# Lamp_Daughter_Board_V0_1.net
KiCad netlist of a schematic drawn in EasyEDA Pro
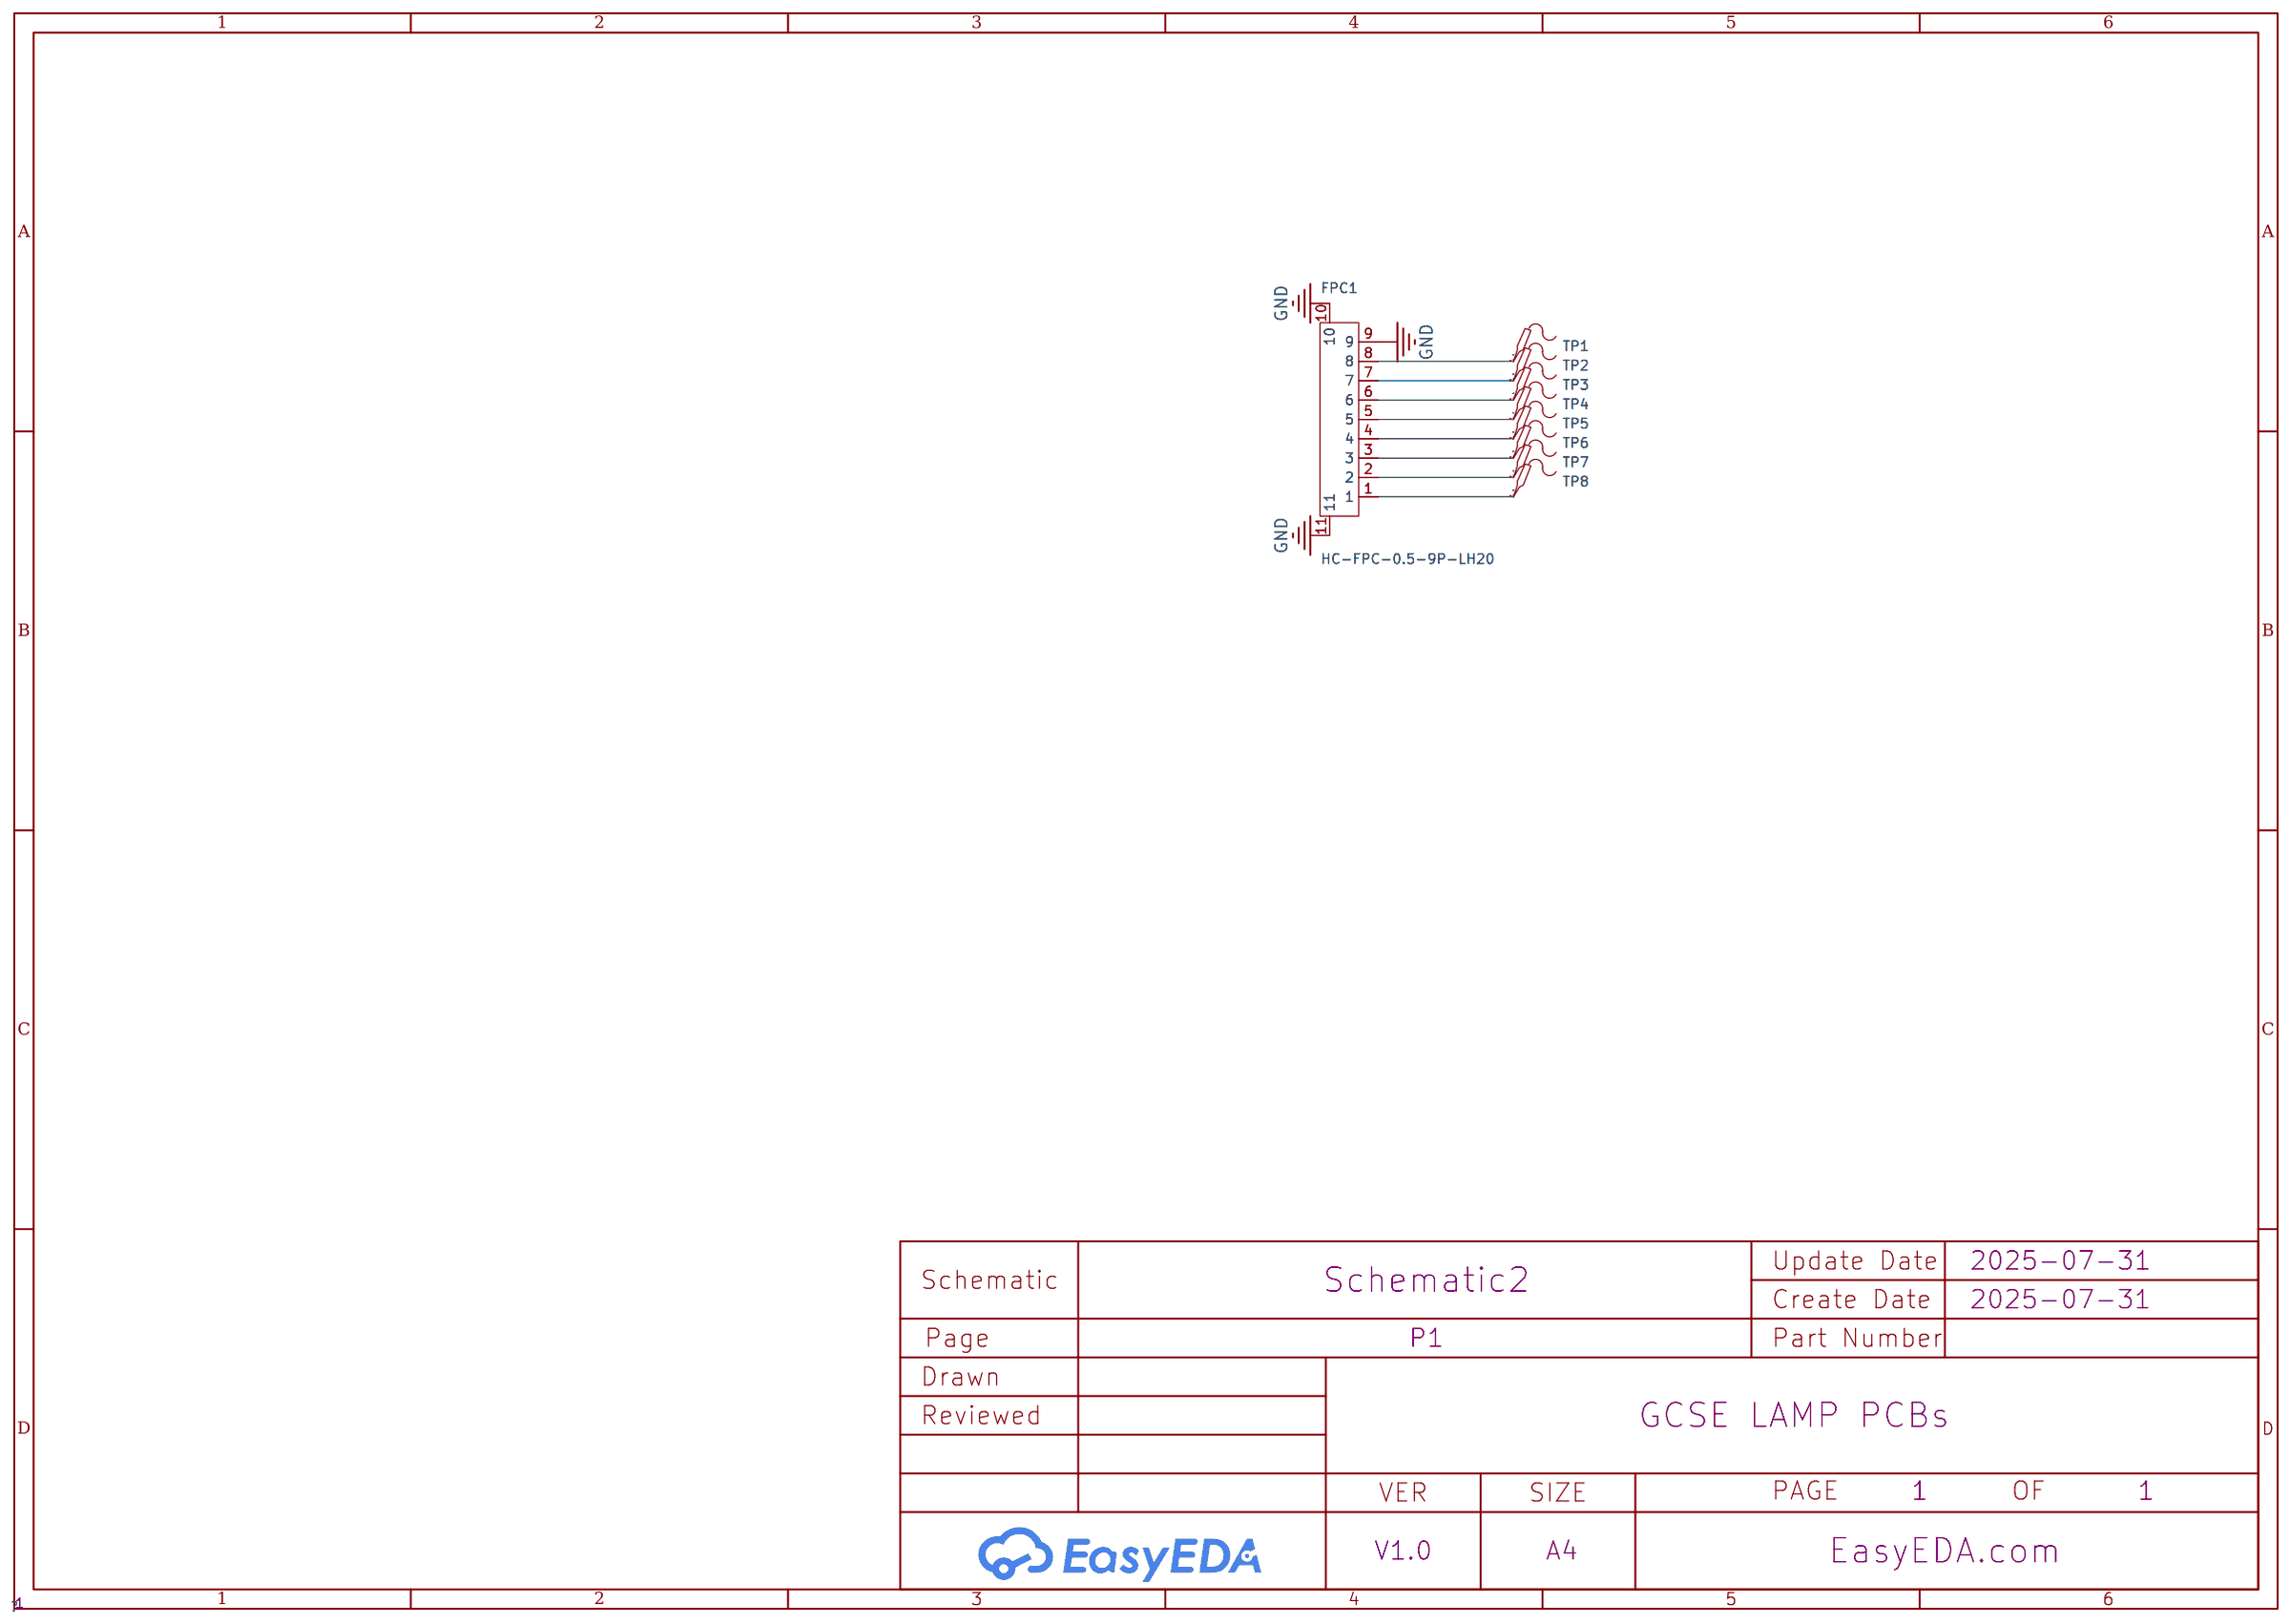
[diagram p0: schematic sheet]

(export (version "E")
  (design (tool "Eeschema 10.0.6"))
  (components
    (comp (ref "FPC1")
      (value "HC-FPC-0.5-9P-LH20")
      (footprint "easyedapro:FPC-SMD_9P-P0.50_HC-FPC-0.5-9P-LH20")
      (fields (field (name "Manufacturer") "HC(虹成电子)"))
      (libsource (lib "easyedapro") (part "HC-FPC-0.5-9P-LH20"))
    )
    (comp (ref "TP1")
      (value "~")
      (footprint "easyedapro:Test-Point-0.5mm")
      (description "Test Point 测试点")
      (libsource (lib "easyedapro") (part "Test-Point"))
    )
    (comp (ref "TP2")
      (value "~")
      (footprint "easyedapro:Test-Point-0.5mm")
      (description "Test Point 测试点")
      (libsource (lib "easyedapro") (part "Test-Point"))
    )
    (comp (ref "TP3")
      (value "~")
      (footprint "easyedapro:Test-Point-0.5mm")
      (description "Test Point 测试点")
      (libsource (lib "easyedapro") (part "Test-Point"))
    )
    (comp (ref "TP4")
      (value "~")
      (footprint "easyedapro:Test-Point-0.5mm")
      (description "Test Point 测试点")
      (libsource (lib "easyedapro") (part "Test-Point"))
    )
    (comp (ref "TP5")
      (value "~")
      (footprint "easyedapro:Test-Point-0.5mm")
      (description "Test Point 测试点")
      (libsource (lib "easyedapro") (part "Test-Point"))
    )
    (comp (ref "TP6")
      (value "~")
      (footprint "easyedapro:Test-Point-0.5mm")
      (description "Test Point 测试点")
      (libsource (lib "easyedapro") (part "Test-Point"))
    )
    (comp (ref "TP7")
      (value "~")
      (footprint "easyedapro:Test-Point-0.5mm")
      (description "Test Point 测试点")
      (libsource (lib "easyedapro") (part "Test-Point"))
    )
    (comp (ref "TP8")
      (value "~")
      (footprint "easyedapro:Test-Point-0.5mm")
      (description "Test Point 测试点")
      (libsource (lib "easyedapro") (part "Test-Point"))
    )
  )
  (nets
    (net (code "1") (name "GND") (class "Default")
      (node (ref "FPC1") (pin "10") (pinfunction "10_10") (pintype "unspecified"))
      (node (ref "FPC1") (pin "11") (pinfunction "11_11") (pintype "unspecified"))
      (node (ref "FPC1") (pin "9") (pinfunction "9_9") (pintype "unspecified"))
    )
    (net (code "2") (name "Net-(FPC1-Pad1)") (class "Default")
      (node (ref "FPC1") (pin "1") (pinfunction "1_1") (pintype "unspecified"))
      (node (ref "TP8") (pin "1") (pinfunction "1_1") (pintype "unspecified"))
    )
    (net (code "3") (name "Net-(FPC1-Pad2)") (class "Default")
      (node (ref "FPC1") (pin "2") (pinfunction "2_2") (pintype "unspecified"))
      (node (ref "TP7") (pin "1") (pinfunction "1_1") (pintype "unspecified"))
    )
    (net (code "4") (name "Net-(FPC1-Pad3)") (class "Default")
      (node (ref "FPC1") (pin "3") (pinfunction "3_3") (pintype "unspecified"))
      (node (ref "TP6") (pin "1") (pinfunction "1_1") (pintype "unspecified"))
    )
    (net (code "5") (name "Net-(FPC1-Pad4)") (class "Default")
      (node (ref "FPC1") (pin "4") (pinfunction "4_4") (pintype "unspecified"))
      (node (ref "TP5") (pin "1") (pinfunction "1_1") (pintype "unspecified"))
    )
    (net (code "6") (name "Net-(FPC1-Pad5)") (class "Default")
      (node (ref "FPC1") (pin "5") (pinfunction "5_5") (pintype "unspecified"))
      (node (ref "TP4") (pin "1") (pinfunction "1_1") (pintype "unspecified"))
    )
    (net (code "7") (name "Net-(FPC1-Pad6)") (class "Default")
      (node (ref "FPC1") (pin "6") (pinfunction "6_6") (pintype "unspecified"))
      (node (ref "TP3") (pin "1") (pinfunction "1_1") (pintype "unspecified"))
    )
    (net (code "8") (name "Net-(FPC1-Pad7)") (class "Default")
      (node (ref "FPC1") (pin "7") (pinfunction "7_7") (pintype "unspecified"))
      (node (ref "TP2") (pin "1") (pinfunction "1_1") (pintype "unspecified"))
    )
    (net (code "9") (name "Net-(FPC1-Pad8)") (class "Default")
      (node (ref "FPC1") (pin "8") (pinfunction "8_8") (pintype "unspecified"))
      (node (ref "TP1") (pin "1") (pinfunction "1_1") (pintype "unspecified"))
    )
  )
)
